# BlueBox-Amp_CrossOver.net
KiCad netlist of a schematic drawn in Altium Designer
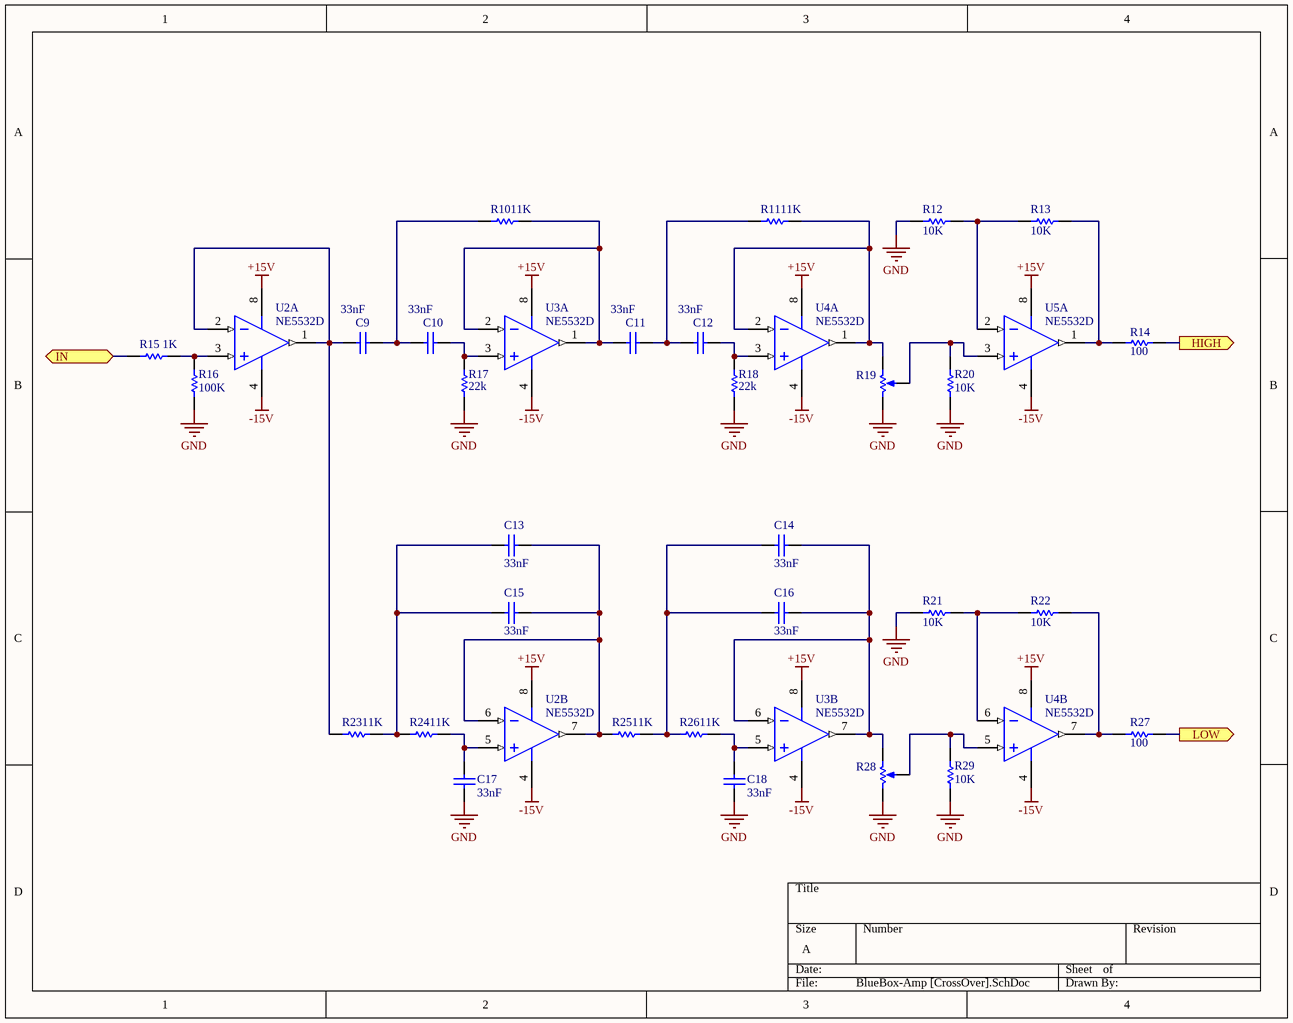
[diagram p0: BlueBox-Amp [CrossOver].SchDoc]

(export (version "E")
  (design (tool "Eeschema 10.0.6"))
  (components
    (comp (ref "C9")
      (value "33nF")
      (footprint "CAPC0603(1608)100_N")
      (description "CAP 33nF 50V ±5% 0603 (1608 Metric) Thickness 1mm SMD")
      (fields (field (name "TOLERANCE") "±5%") (field (name "Comment") "CAP 33nF 50V 0603(1608)"))
      (libsource (lib "Altium Content Vault") (part "CMP-1035-02468-1"))
    )
    (comp (ref "C10")
      (value "33nF")
      (footprint "CAPC0603(1608)100_N")
      (description "CAP 33nF 50V ±5% 0603 (1608 Metric) Thickness 1mm SMD")
      (fields (field (name "TOLERANCE") "±5%") (field (name "Comment") "CAP 33nF 50V 0603(1608)"))
      (libsource (lib "Altium Content Vault") (part "CMP-1035-02468-1"))
    )
    (comp (ref "C11")
      (value "33nF")
      (footprint "CAPC0603(1608)100_N")
      (description "CAP 33nF 50V ±5% 0603 (1608 Metric) Thickness 1mm SMD")
      (fields (field (name "TOLERANCE") "±5%") (field (name "Comment") "CAP 33nF 50V 0603(1608)"))
      (libsource (lib "Altium Content Vault") (part "CMP-1035-02468-1"))
    )
    (comp (ref "C12")
      (value "33nF")
      (footprint "CAPC0603(1608)100_N")
      (description "CAP 33nF 50V ±5% 0603 (1608 Metric) Thickness 1mm SMD")
      (fields (field (name "TOLERANCE") "±5%") (field (name "Comment") "CAP 33nF 50V 0603(1608)"))
      (libsource (lib "Altium Content Vault") (part "CMP-1035-02468-1"))
    )
    (comp (ref "C13")
      (value "33nF")
      (footprint "CAPC0603(1608)100_N")
      (description "CAP 33nF 50V ±5% 0603 (1608 Metric) Thickness 1mm SMD")
      (fields (field (name "TOLERANCE") "±5%") (field (name "Comment") "CAP 33nF 50V 0603(1608)"))
      (libsource (lib "Altium Content Vault") (part "CMP-1035-02468-1"))
    )
    (comp (ref "C14")
      (value "33nF")
      (footprint "CAPC0603(1608)100_N")
      (description "CAP 33nF 50V ±5% 0603 (1608 Metric) Thickness 1mm SMD")
      (fields (field (name "TOLERANCE") "±5%") (field (name "Comment") "CAP 33nF 50V 0603(1608)"))
      (libsource (lib "Altium Content Vault") (part "CMP-1035-02468-1"))
    )
    (comp (ref "C15")
      (value "33nF")
      (footprint "CAPC0603(1608)100_N")
      (description "CAP 33nF 50V ±5% 0603 (1608 Metric) Thickness 1mm SMD")
      (fields (field (name "TOLERANCE") "±5%") (field (name "Comment") "CAP 33nF 50V 0603(1608)"))
      (libsource (lib "Altium Content Vault") (part "CMP-1035-02468-1"))
    )
    (comp (ref "C16")
      (value "33nF")
      (footprint "CAPC0603(1608)100_N")
      (description "CAP 33nF 50V ±5% 0603 (1608 Metric) Thickness 1mm SMD")
      (fields (field (name "TOLERANCE") "±5%") (field (name "Comment") "CAP 33nF 50V 0603(1608)"))
      (libsource (lib "Altium Content Vault") (part "CMP-1035-02468-1"))
    )
    (comp (ref "C17")
      (value "33nF")
      (footprint "CAPC0603(1608)100_N")
      (description "CAP 33nF 50V ±5% 0603 (1608 Metric) Thickness 1mm SMD")
      (fields (field (name "TOLERANCE") "±5%") (field (name "Comment") "CAP 33nF 50V 0603(1608)"))
      (libsource (lib "Altium Content Vault") (part "CMP-1035-02468-1"))
    )
    (comp (ref "C18")
      (value "33nF")
      (footprint "CAPC0603(1608)100_N")
      (description "CAP 33nF 50V ±5% 0603 (1608 Metric) Thickness 1mm SMD")
      (fields (field (name "TOLERANCE") "±5%") (field (name "Comment") "CAP 33nF 50V 0603(1608)"))
      (libsource (lib "Altium Content Vault") (part "CMP-1035-02468-1"))
    )
    (comp (ref "R10")
      (value "11K")
      (footprint "RESC0603(1608)_M")
      (description "11K 0.1W 1% 0603 (1608 Metric)  SMD")
      (fields (field (name "POWER") "0.1 W") (field (name "TOLERANCE") "1 %"))
      (libsource (lib "Altium Content Vault") (part "CMP-1012-00627-1"))
    )
    (comp (ref "R11")
      (value "11K")
      (footprint "RESC0603(1608)_M")
      (description "11K 0.1W 1% 0603 (1608 Metric)  SMD")
      (fields (field (name "POWER") "0.1 W") (field (name "TOLERANCE") "1 %"))
      (libsource (lib "Altium Content Vault") (part "CMP-1012-00627-1"))
    )
    (comp (ref "R12")
      (value "10K")
      (footprint "RESC0603(1608)_N")
      (description "10K 0.1W 1% 0603 (1608 Metric)  SMD")
      (fields (field (name "POWER") "0.1 W") (field (name "TOLERANCE") "1 %"))
      (libsource (lib "Altium Content Vault") (part "CMP-1012-00623-1"))
    )
    (comp (ref "R13")
      (value "10K")
      (footprint "RESC0603(1608)_N")
      (description "10K 0.1W 1% 0603 (1608 Metric)  SMD")
      (fields (field (name "POWER") "0.1 W") (field (name "TOLERANCE") "1 %"))
      (libsource (lib "Altium Content Vault") (part "CMP-1012-00623-1"))
    )
    (comp (ref "R14")
      (value "100")
      (footprint "RESC0603(1608)_M")
      (description "100R 0.1W 1% 0603 (1608 Metric)  SMD")
      (fields (field (name "TOLERANCE") "1 %") (field (name "POWER") "0.1 W"))
      (libsource (lib "Altium Content Vault") (part "CMP-1012-00397-1"))
    )
    (comp (ref "R15")
      (value "1K")
      (footprint "RESC0603(1608)_M")
      (description "1K 0.1W 1% 0603 (1608 Metric)  SMD")
      (fields (field (name "TOLERANCE") "1 %") (field (name "POWER") "0.1 W"))
      (libsource (lib "Altium Content Vault") (part "CMP-1012-00510-1"))
    )
    (comp (ref "R16")
      (value "100K")
      (footprint "RESC0603(1608)_N")
      (description "100K 0.1W 1% 0603 (1608 Metric)  SMD")
      (fields (field (name "POWER") "0.1 W") (field (name "TOLERANCE") "1 %"))
      (libsource (lib "Altium Content Vault") (part "CMP-1012-00736-1"))
    )
    (comp (ref "R17")
      (value "22k")
      (footprint "RESC0603(1608)_L")
      (description "22K 0.1W 1% 0603 (1608 Metric)  SMD")
      (fields (field (name "POWER") "0.1 W") (field (name "TOLERANCE") "1 %"))
      (libsource (lib "Altium Content Vault") (part "CMP-1012-00659-1"))
    )
    (comp (ref "R18")
      (value "22k")
      (footprint "RESC0603(1608)_L")
      (description "22K 0.1W 1% 0603 (1608 Metric)  SMD")
      (fields (field (name "POWER") "0.1 W") (field (name "TOLERANCE") "1 %"))
      (libsource (lib "Altium Content Vault") (part "CMP-1012-00659-1"))
    )
    (comp (ref "R19")
      (value "3266W-1-104LF")
      (footprint "BOUR-3266W-3_V")
      (description "Square Trimpot Trimming Potentiometer, 100 KOhm, 0.25 W, -55 to 125 degC, 3-Pin THD, RoHS, Tube")
      (fields (field (name "TOLERANCE") "+/-10%") (field (name "MANUFACTURER") "Bourns"))
      (libsource (lib "Altium Content Vault") (part "CMP-0975-00021-1"))
    )
    (comp (ref "R20")
      (value "10K")
      (footprint "RESC0603(1608)_N")
      (description "10K 0.1W 1% 0603 (1608 Metric)  SMD")
      (fields (field (name "POWER") "0.1 W") (field (name "TOLERANCE") "1 %"))
      (libsource (lib "Altium Content Vault") (part "CMP-1012-00623-1"))
    )
    (comp (ref "R21")
      (value "10K")
      (footprint "RESC0603(1608)_N")
      (description "10K 0.1W 1% 0603 (1608 Metric)  SMD")
      (fields (field (name "POWER") "0.1 W") (field (name "TOLERANCE") "1 %"))
      (libsource (lib "Altium Content Vault") (part "CMP-1012-00623-1"))
    )
    (comp (ref "R22")
      (value "10K")
      (footprint "RESC0603(1608)_N")
      (description "10K 0.1W 1% 0603 (1608 Metric)  SMD")
      (fields (field (name "POWER") "0.1 W") (field (name "TOLERANCE") "1 %"))
      (libsource (lib "Altium Content Vault") (part "CMP-1012-00623-1"))
    )
    (comp (ref "R23")
      (value "11K")
      (footprint "RESC0603(1608)_M")
      (description "11K 0.1W 1% 0603 (1608 Metric)  SMD")
      (fields (field (name "POWER") "0.1 W") (field (name "TOLERANCE") "1 %"))
      (libsource (lib "Altium Content Vault") (part "CMP-1012-00627-1"))
    )
    (comp (ref "R24")
      (value "11K")
      (footprint "RESC0603(1608)_M")
      (description "11K 0.1W 1% 0603 (1608 Metric)  SMD")
      (fields (field (name "POWER") "0.1 W") (field (name "TOLERANCE") "1 %"))
      (libsource (lib "Altium Content Vault") (part "CMP-1012-00627-1"))
    )
    (comp (ref "R25")
      (value "11K")
      (footprint "RESC0603(1608)_M")
      (description "11K 0.1W 1% 0603 (1608 Metric)  SMD")
      (fields (field (name "POWER") "0.1 W") (field (name "TOLERANCE") "1 %"))
      (libsource (lib "Altium Content Vault") (part "CMP-1012-00627-1"))
    )
    (comp (ref "R26")
      (value "11K")
      (footprint "RESC0603(1608)_M")
      (description "11K 0.1W 1% 0603 (1608 Metric)  SMD")
      (fields (field (name "POWER") "0.1 W") (field (name "TOLERANCE") "1 %"))
      (libsource (lib "Altium Content Vault") (part "CMP-1012-00627-1"))
    )
    (comp (ref "R27")
      (value "100")
      (footprint "RESC0603(1608)_M")
      (description "100R 0.1W 1% 0603 (1608 Metric)  SMD")
      (fields (field (name "TOLERANCE") "1 %") (field (name "POWER") "0.1 W"))
      (libsource (lib "Altium Content Vault") (part "CMP-1012-00397-1"))
    )
    (comp (ref "R28")
      (value "3266W-1-104LF")
      (footprint "BOUR-3266W-3_V")
      (description "Square Trimpot Trimming Potentiometer, 100 KOhm, 0.25 W, -55 to 125 degC, 3-Pin THD, RoHS, Tube")
      (fields (field (name "TOLERANCE") "+/-10%") (field (name "MANUFACTURER") "Bourns"))
      (libsource (lib "Altium Content Vault") (part "CMP-0975-00021-1"))
    )
    (comp (ref "R29")
      (value "10K")
      (footprint "RESC0603(1608)_N")
      (description "10K 0.1W 1% 0603 (1608 Metric)  SMD")
      (fields (field (name "POWER") "0.1 W") (field (name "TOLERANCE") "1 %"))
      (libsource (lib "Altium Content Vault") (part "CMP-1012-00623-1"))
    )
    (comp (ref "U2")
      (value "NE5532D")
      (footprint "TI-D8_M")
      (fields (field (name "MANUFACTURER") "Texas Instruments"))
      (libsource (lib "Altium Content Vault") (part "CMP-0015-00060-1"))
    )
    (comp (ref "U3")
      (value "NE5532D")
      (footprint "TI-D8_M")
      (fields (field (name "MANUFACTURER") "Texas Instruments"))
      (libsource (lib "Altium Content Vault") (part "CMP-0015-00060-1"))
    )
    (comp (ref "U4")
      (value "NE5532D")
      (footprint "TI-D8_M")
      (fields (field (name "MANUFACTURER") "Texas Instruments"))
      (libsource (lib "Altium Content Vault") (part "CMP-0015-00060-1"))
    )
    (comp (ref "U5")
      (value "NE5532D")
      (footprint "TI-D8_M")
      (fields (field (name "MANUFACTURER") "Texas Instruments"))
      (libsource (lib "Altium Content Vault") (part "CMP-0015-00060-1"))
    )
  )
  (nets
    (net (code "1") (name "+15V") (class "Default")
      (node (ref "U2") (pin "8") (pinfunction "VCC+_8") (pintype "power_in"))
      (node (ref "U3") (pin "8") (pinfunction "VCC+_8") (pintype "power_in"))
      (node (ref "U4") (pin "8") (pinfunction "VCC+_8") (pintype "power_in"))
      (node (ref "U5") (pin "8") (pinfunction "VCC+_8") (pintype "power_in"))
    )
    (net (code "2") (name "-15V") (class "Default")
      (node (ref "U2") (pin "4") (pinfunction "VCC-_4") (pintype "power_in"))
      (node (ref "U3") (pin "4") (pinfunction "VCC-_4") (pintype "power_in"))
      (node (ref "U4") (pin "4") (pinfunction "VCC-_4") (pintype "power_in"))
      (node (ref "U5") (pin "4") (pinfunction "VCC-_4") (pintype "power_in"))
    )
    (net (code "3") (name "/HIGH") (class "Default")
      (node (ref "R14") (pin "2") (pinfunction "2_2") (pintype "passive"))
    )
    (net (code "4") (name "/IN") (class "Default")
      (node (ref "R15") (pin "1") (pinfunction "1_1") (pintype "passive"))
    )
    (net (code "5") (name "/LOW") (class "Default")
      (node (ref "R27") (pin "2") (pinfunction "2_2") (pintype "passive"))
    )
    (net (code "6") (name "GND") (class "Default")
      (node (ref "C17") (pin "1") (pinfunction "1_1") (pintype "passive"))
      (node (ref "C18") (pin "1") (pinfunction "1_1") (pintype "passive"))
      (node (ref "R12") (pin "1") (pinfunction "1_1") (pintype "passive"))
      (node (ref "R16") (pin "1") (pinfunction "1_1") (pintype "passive"))
      (node (ref "R17") (pin "1") (pinfunction "1_1") (pintype "passive"))
      (node (ref "R18") (pin "1") (pinfunction "1_1") (pintype "passive"))
      (node (ref "R19") (pin "3") (pinfunction "CW_3") (pintype "passive"))
      (node (ref "R20") (pin "2") (pinfunction "2_2") (pintype "passive"))
      (node (ref "R21") (pin "1") (pinfunction "1_1") (pintype "passive"))
      (node (ref "R28") (pin "3") (pinfunction "CW_3") (pintype "passive"))
      (node (ref "R29") (pin "2") (pinfunction "2_2") (pintype "passive"))
    )
    (net (code "7") (name "Net-(C10-Pad1)") (class "Default")
      (node (ref "C10") (pin "1") (pinfunction "1_1") (pintype "passive"))
      (node (ref "C9") (pin "2") (pinfunction "2_2") (pintype "passive"))
      (node (ref "R10") (pin "1") (pinfunction "1_1") (pintype "passive"))
    )
    (net (code "8") (name "Net-(C11-Pad2)") (class "Default")
      (node (ref "C11") (pin "2") (pinfunction "2_2") (pintype "passive"))
      (node (ref "C12") (pin "1") (pinfunction "1_1") (pintype "passive"))
      (node (ref "R11") (pin "1") (pinfunction "1_1") (pintype "passive"))
    )
    (net (code "9") (name "Net-(C13-Pad2)") (class "Default")
      (node (ref "C13") (pin "2") (pinfunction "2_2") (pintype "passive"))
      (node (ref "C15") (pin "2") (pinfunction "2_2") (pintype "passive"))
      (node (ref "R23") (pin "2") (pinfunction "2_2") (pintype "passive"))
      (node (ref "R24") (pin "1") (pinfunction "1_1") (pintype "passive"))
    )
    (net (code "10") (name "Net-(C14-Pad2)") (class "Default")
      (node (ref "C14") (pin "2") (pinfunction "2_2") (pintype "passive"))
      (node (ref "C16") (pin "2") (pinfunction "2_2") (pintype "passive"))
      (node (ref "R25") (pin "2") (pinfunction "2_2") (pintype "passive"))
      (node (ref "R26") (pin "1") (pinfunction "1_1") (pintype "passive"))
    )
    (net (code "11") (name "Net-(R19-CCW)") (class "Default")
      (node (ref "R11") (pin "2") (pinfunction "2_2") (pintype "passive"))
      (node (ref "R19") (pin "1") (pinfunction "CCW_1") (pintype "passive"))
      (node (ref "U4") (pin "1") (pinfunction "OUT1_1") (pintype "output"))
      (node (ref "U4") (pin "2") (pinfunction "IN1-_2") (pintype "input"))
    )
    (net (code "12") (name "Net-(R19-WIPER)") (class "Default")
      (node (ref "R19") (pin "2") (pinfunction "WIPER_2") (pintype "passive"))
      (node (ref "R20") (pin "1") (pinfunction "1_1") (pintype "passive"))
      (node (ref "U5") (pin "3") (pinfunction "IN1+_3") (pintype "input"))
    )
    (net (code "13") (name "Net-(R28-CCW)") (class "Default")
      (node (ref "C14") (pin "1") (pinfunction "1_1") (pintype "passive"))
      (node (ref "C16") (pin "1") (pinfunction "1_1") (pintype "passive"))
      (node (ref "R28") (pin "1") (pinfunction "CCW_1") (pintype "passive"))
      (node (ref "U3") (pin "6") (pinfunction "IN2-_6") (pintype "input"))
      (node (ref "U3") (pin "7") (pinfunction "OUT2_7") (pintype "output"))
    )
    (net (code "14") (name "Net-(R28-WIPER)") (class "Default")
      (node (ref "R28") (pin "2") (pinfunction "WIPER_2") (pintype "passive"))
      (node (ref "R29") (pin "1") (pinfunction "1_1") (pintype "passive"))
      (node (ref "U4") (pin "5") (pinfunction "IN2+_5") (pintype "input"))
    )
    (net (code "15") (name "Net-(U2A-IN1+)") (class "Default")
      (node (ref "R15") (pin "2") (pinfunction "2_2") (pintype "passive"))
      (node (ref "R16") (pin "2") (pinfunction "2_2") (pintype "passive"))
      (node (ref "U2") (pin "3") (pinfunction "IN1+_3") (pintype "input"))
    )
    (net (code "16") (name "Net-(U2A-IN1-)") (class "Default")
      (node (ref "C9") (pin "1") (pinfunction "1_1") (pintype "passive"))
      (node (ref "R23") (pin "1") (pinfunction "1_1") (pintype "passive"))
      (node (ref "U2") (pin "1") (pinfunction "OUT1_1") (pintype "output"))
      (node (ref "U2") (pin "2") (pinfunction "IN1-_2") (pintype "input"))
    )
    (net (code "17") (name "Net-(U2B-IN2+)") (class "Default")
      (node (ref "C17") (pin "2") (pinfunction "2_2") (pintype "passive"))
      (node (ref "R24") (pin "2") (pinfunction "2_2") (pintype "passive"))
      (node (ref "U2") (pin "5") (pinfunction "IN2+_5") (pintype "input"))
    )
    (net (code "18") (name "Net-(U2B-IN2-)") (class "Default")
      (node (ref "C13") (pin "1") (pinfunction "1_1") (pintype "passive"))
      (node (ref "C15") (pin "1") (pinfunction "1_1") (pintype "passive"))
      (node (ref "R25") (pin "1") (pinfunction "1_1") (pintype "passive"))
      (node (ref "U2") (pin "6") (pinfunction "IN2-_6") (pintype "input"))
      (node (ref "U2") (pin "7") (pinfunction "OUT2_7") (pintype "output"))
    )
    (net (code "19") (name "Net-(U3A-IN1+)") (class "Default")
      (node (ref "C10") (pin "2") (pinfunction "2_2") (pintype "passive"))
      (node (ref "R17") (pin "2") (pinfunction "2_2") (pintype "passive"))
      (node (ref "U3") (pin "3") (pinfunction "IN1+_3") (pintype "input"))
    )
    (net (code "20") (name "Net-(U3A-IN1-)") (class "Default")
      (node (ref "C11") (pin "1") (pinfunction "1_1") (pintype "passive"))
      (node (ref "R10") (pin "2") (pinfunction "2_2") (pintype "passive"))
      (node (ref "U3") (pin "1") (pinfunction "OUT1_1") (pintype "output"))
      (node (ref "U3") (pin "2") (pinfunction "IN1-_2") (pintype "input"))
    )
    (net (code "21") (name "Net-(U3B-IN2+)") (class "Default")
      (node (ref "C18") (pin "2") (pinfunction "2_2") (pintype "passive"))
      (node (ref "R26") (pin "2") (pinfunction "2_2") (pintype "passive"))
      (node (ref "U3") (pin "5") (pinfunction "IN2+_5") (pintype "input"))
    )
    (net (code "22") (name "Net-(U4A-IN1+)") (class "Default")
      (node (ref "C12") (pin "2") (pinfunction "2_2") (pintype "passive"))
      (node (ref "R18") (pin "2") (pinfunction "2_2") (pintype "passive"))
      (node (ref "U4") (pin "3") (pinfunction "IN1+_3") (pintype "input"))
    )
    (net (code "23") (name "Net-(U4B-IN2-)") (class "Default")
      (node (ref "R21") (pin "2") (pinfunction "2_2") (pintype "passive"))
      (node (ref "R22") (pin "1") (pinfunction "1_1") (pintype "passive"))
      (node (ref "U4") (pin "6") (pinfunction "IN2-_6") (pintype "input"))
    )
    (net (code "24") (name "Net-(U4B-OUT2)") (class "Default")
      (node (ref "R22") (pin "2") (pinfunction "2_2") (pintype "passive"))
      (node (ref "R27") (pin "1") (pinfunction "1_1") (pintype "passive"))
      (node (ref "U4") (pin "7") (pinfunction "OUT2_7") (pintype "output"))
    )
    (net (code "25") (name "Net-(U5A-IN1-)") (class "Default")
      (node (ref "R12") (pin "2") (pinfunction "2_2") (pintype "passive"))
      (node (ref "R13") (pin "1") (pinfunction "1_1") (pintype "passive"))
      (node (ref "U5") (pin "2") (pinfunction "IN1-_2") (pintype "input"))
    )
    (net (code "26") (name "Net-(U5A-OUT1)") (class "Default")
      (node (ref "R13") (pin "2") (pinfunction "2_2") (pintype "passive"))
      (node (ref "R14") (pin "1") (pinfunction "1_1") (pintype "passive"))
      (node (ref "U5") (pin "1") (pinfunction "OUT1_1") (pintype "output"))
    )
  )
)
